# A4_INSAGE_02.net
KiCad netlist of a schematic drawn in Altium Designer
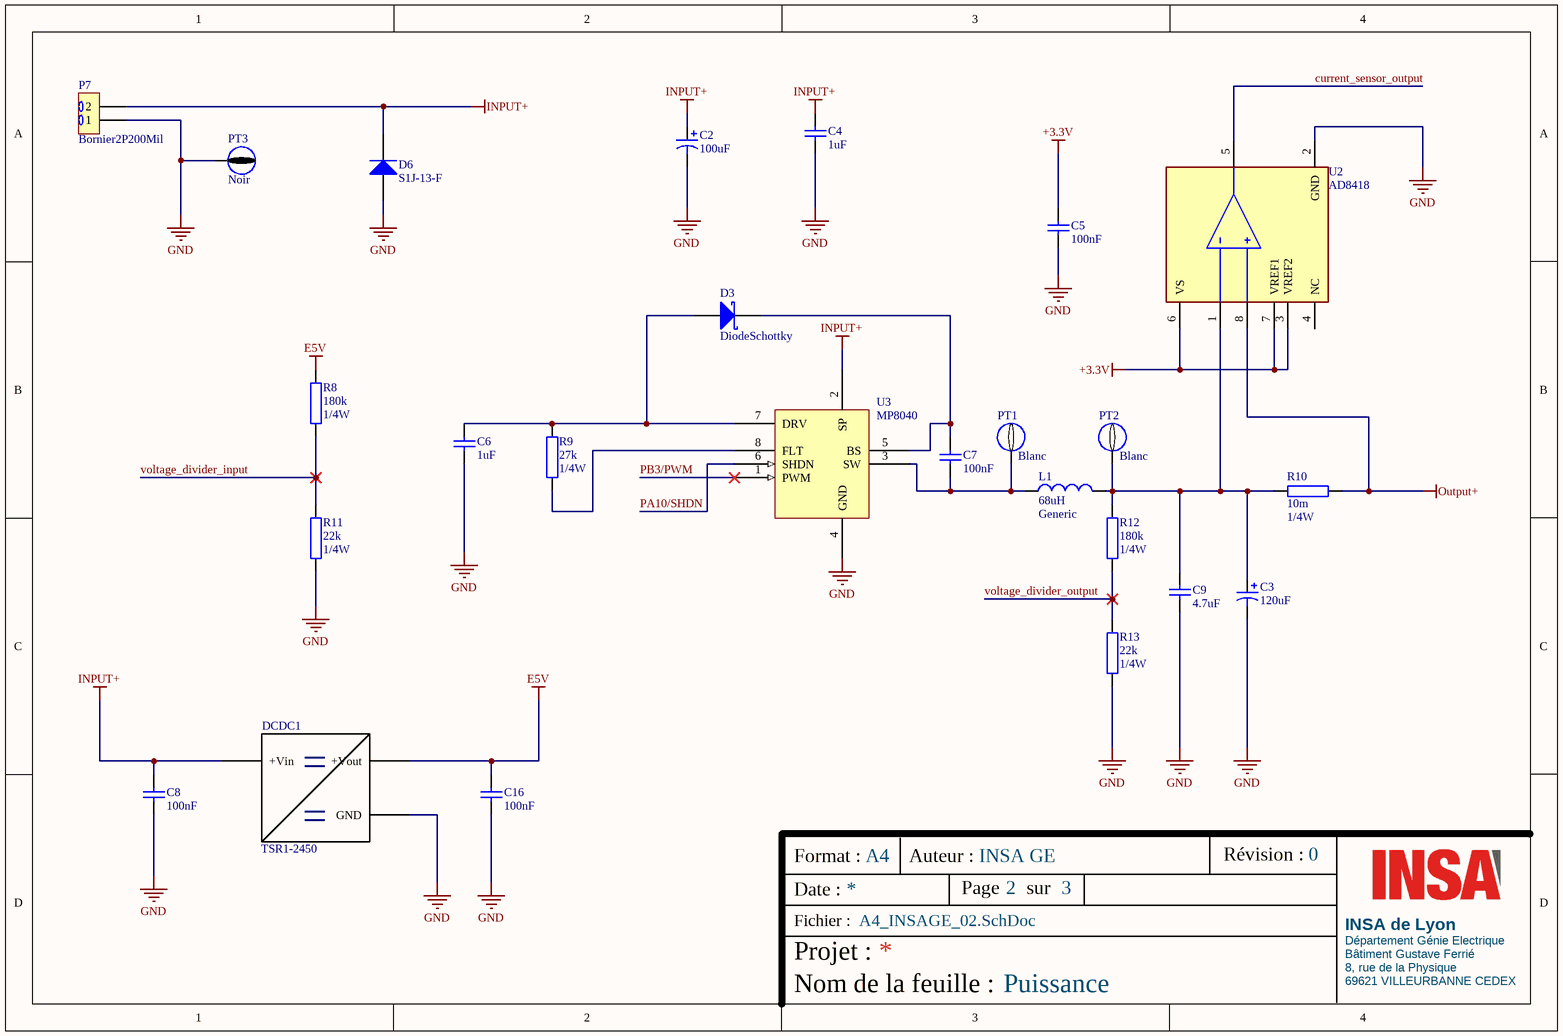
[diagram p0: A4_INSAGE_02.SchDoc]

(export (version "E")
  (design (tool "Eeschema 10.0.6"))
  (components
    (comp (ref "C2")
      (value "100uF")
      (footprint "CAPRAD10diax9.5")
      (fields (field (name "Comment") "Condensateur Pol") (field (name "PUBLISHER") "Altium Limited"))
      (libsource (lib "Altium_CREATE_2026") (part "Condensateur Pol"))
    )
    (comp (ref "C3")
      (value "120uF")
      (footprint "CAPRAD10diax9.5")
      (fields (field (name "Comment") "Condensateur Pol") (field (name "PUBLISHER") "Altium Limited"))
      (libsource (lib "Altium_CREATE_2026") (part "Condensateur Pol"))
    )
    (comp (ref "C4")
      (value "1uF")
      (footprint "1206_C")
      (fields (field (name "Comment") "Condensateur NON pol") (field (name "PUBLISHER") "Altium Limited"))
      (libsource (lib "Altium_CREATE_2026") (part "Condensateur NON pol"))
    )
    (comp (ref "C5")
      (value "100nF")
      (footprint "1206_C")
      (fields (field (name "Comment") "Condensateur NON pol") (field (name "PUBLISHER") "Altium Limited"))
      (libsource (lib "Altium_CREATE_2026") (part "Condensateur NON pol"))
    )
    (comp (ref "C6")
      (value "1uF")
      (footprint "1206_C")
      (fields (field (name "Comment") "Condensateur NON pol") (field (name "PUBLISHER") "Altium Limited"))
      (libsource (lib "Altium_CREATE_2026") (part "Condensateur NON pol"))
    )
    (comp (ref "C7")
      (value "100nF")
      (footprint "1206_C")
      (fields (field (name "Comment") "Condensateur NON pol") (field (name "PUBLISHER") "Altium Limited"))
      (libsource (lib "Altium_CREATE_2026") (part "Condensateur NON pol"))
    )
    (comp (ref "C8")
      (value "100nF")
      (footprint "1206_C")
      (fields (field (name "Comment") "Condensateur NON pol") (field (name "PUBLISHER") "Altium Limited"))
      (libsource (lib "Altium_CREATE_2026") (part "Condensateur NON pol"))
    )
    (comp (ref "C9")
      (value "4.7uF")
      (footprint "1206_C")
      (fields (field (name "Comment") "Condensateur NON pol") (field (name "PUBLISHER") "Altium Limited"))
      (libsource (lib "Altium_CREATE_2026") (part "Condensateur NON pol"))
    )
    (comp (ref "C16")
      (value "100nF")
      (footprint "1206_C")
      (fields (field (name "Comment") "Condensateur NON pol") (field (name "PUBLISHER") "Altium Limited"))
      (libsource (lib "Altium_CREATE_2026") (part "Condensateur NON pol"))
    )
    (comp (ref "D3")
      (value "DiodeSchottky")
      (footprint "DO-41")
      (description "Low drop power Schottky rectifier")
      (fields (field (name "PUBLISHER") "Altium Limited"))
      (libsource (lib "Altium_CREATE_2026") (part "1N5819"))
    )
    (comp (ref "D6")
      (value "S1J-13-F")
      (footprint "SMA (DO-214AC)")
      (description "Diode standard de redressement 600V 1A")
      (libsource (lib "Altium_CREATE_2026") (part "S1J-13-F"))
    )
    (comp (ref "DCDC1")
      (value "TSR1-2450")
      (footprint "TSR1Serie-1A")
      (description "DC/DC 6,5/36 -> 5V 1A")
      (libsource (lib "Altium_CREATE_2026") (part "TSR1-2450"))
    )
    (comp (ref "L1")
      (value "Generic")
      (footprint "7447709680")
      (description "Inductance 7447709680 Würth")
      (fields (field (name "ALTIUM_VALUE") "68uH") (field (name "PUBLISHER") "Altium Limited"))
      (libsource (lib "Altium_CREATE_2026") (part "Würth_7447709680"))
    )
    (comp (ref "P7")
      (value "Bornier2P200Mil")
      (footprint "BORN2PIN200MIL")
      (description "Bornier 2P 200mil")
      (fields (field (name "PUBLISHER") "Altium Limited"))
      (libsource (lib "Altium_CREATE_2026") (part "Bornier2P200Mil"))
    )
    (comp (ref "PT1")
      (value "Blanc")
      (footprint "PTest1.32mm")
      (description "Point de test PCB, Blanc, Montage traversant, 1.32 mm")
      (libsource (lib "Altium_CREATE_2026") (part "PTest_Blanc"))
    )
    (comp (ref "PT2")
      (value "Blanc")
      (footprint "PTest1.32mm")
      (description "Point de test PCB, Blanc, Montage traversant, 1.32 mm")
      (libsource (lib "Altium_CREATE_2026") (part "PTest_Blanc"))
    )
    (comp (ref "PT3")
      (value "Noir")
      (footprint "PTest1.32mm")
      (description "Point de test PCB, Noir, Montage traversant, 1.32 mm")
      (libsource (lib "Altium_CREATE_2026") (part "PTest_Noir"))
    )
    (comp (ref "R8")
      (value "180k")
      (footprint "1206_R")
      (description "Resistor")
      (fields
        (field (name "PUISSANCE") "1/4W")
        (field (name "Comment") "Resistance")
        (field (name "PUBLISHER") "Altium Limited")
      )
      (libsource (lib "Altium_CREATE_2026") (part "Resistance"))
    )
    (comp (ref "R9")
      (value "27k")
      (footprint "1206_R")
      (description "Resistor")
      (fields
        (field (name "PUISSANCE") "1/4W")
        (field (name "Comment") "Resistance")
        (field (name "PUBLISHER") "Altium Limited")
      )
      (libsource (lib "Altium_CREATE_2026") (part "Resistance"))
    )
    (comp (ref "R10")
      (value "10m")
      (footprint "1206_R")
      (description "Resistor")
      (fields
        (field (name "PUISSANCE") "1/4W")
        (field (name "Comment") "Resistance")
        (field (name "PUBLISHER") "Altium Limited")
      )
      (libsource (lib "Altium_CREATE_2026") (part "Resistance"))
    )
    (comp (ref "R11")
      (value "22k")
      (footprint "1206_R")
      (description "Resistor")
      (fields
        (field (name "PUISSANCE") "1/4W")
        (field (name "Comment") "Resistance")
        (field (name "PUBLISHER") "Altium Limited")
      )
      (libsource (lib "Altium_CREATE_2026") (part "Resistance"))
    )
    (comp (ref "R12")
      (value "180k")
      (footprint "1206_R")
      (description "Resistor")
      (fields
        (field (name "PUISSANCE") "1/4W")
        (field (name "Comment") "Resistance")
        (field (name "PUBLISHER") "Altium Limited")
      )
      (libsource (lib "Altium_CREATE_2026") (part "Resistance"))
    )
    (comp (ref "R13")
      (value "22k")
      (footprint "1206_R")
      (description "Resistor")
      (fields
        (field (name "PUISSANCE") "1/4W")
        (field (name "Comment") "Resistance")
        (field (name "PUBLISHER") "Altium Limited")
      )
      (libsource (lib "Altium_CREATE_2026") (part "Resistance"))
    )
    (comp (ref "U2")
      (value "AD8418")
      (footprint "SOIC-8-150")
      (description "IC Current Sensor")
      (libsource (lib "Altium_CREATE_2026") (part "AD8418"))
    )
    (comp (ref "U3")
      (value "MP8040")
      (footprint "SOIC-8-150")
      (description "9A, 24V Integrated Half-Bridge")
      (libsource (lib "Altium_CREATE_2026") (part "MP8040"))
    )
  )
  (nets
    (net (code "1") (name "+3.3V") (class "Default")
      (node (ref "C5") (pin "2") (pinfunction "2_2") (pintype "passive"))
      (node (ref "U2") (pin "3") (pinfunction "VREF2_3") (pintype "power_in"))
      (node (ref "U2") (pin "6") (pinfunction "VS_6") (pintype "power_in"))
      (node (ref "U2") (pin "7") (pinfunction "VREF1_7") (pintype "power_in"))
    )
    (net (code "2") (name "/PA10{slash}SHDN") (class "Default")
      (node (ref "U3") (pin "6") (pinfunction "SHDN_6") (pintype "input"))
    )
    (net (code "3") (name "/PB3{slash}PWM") (class "Default")
      (node (ref "U3") (pin "1") (pinfunction "PWM_1") (pintype "input+no_connect"))
    )
    (net (code "4") (name "/current_sensor_output") (class "Default")
      (node (ref "U2") (pin "5") (pinfunction "OUT_5") (pintype "passive"))
    )
    (net (code "5") (name "/voltage_divider_input") (class "Default")
      (node (ref "R11") (pin "2") (pinfunction "2_2") (pintype "passive"))
      (node (ref "R8") (pin "1") (pinfunction "1_1") (pintype "passive"))
    )
    (net (code "6") (name "/voltage_divider_output") (class "Default")
      (node (ref "R12") (pin "1") (pinfunction "1_1") (pintype "passive"))
      (node (ref "R13") (pin "2") (pinfunction "2_2") (pintype "passive"))
    )
    (net (code "7") (name "E5V") (class "Default")
      (node (ref "C16") (pin "2") (pinfunction "2_2") (pintype "passive"))
      (node (ref "DCDC1") (pin "3") (pinfunction "+Vout_3") (pintype "power_in"))
      (node (ref "R8") (pin "2") (pinfunction "2_2") (pintype "passive"))
    )
    (net (code "8") (name "GND") (class "Default")
      (node (ref "C16") (pin "1") (pinfunction "1_1") (pintype "passive"))
      (node (ref "C2") (pin "2") (pinfunction "2_2") (pintype "passive"))
      (node (ref "C3") (pin "2") (pinfunction "2_2") (pintype "passive"))
      (node (ref "C4") (pin "1") (pinfunction "1_1") (pintype "passive"))
      (node (ref "C5") (pin "1") (pinfunction "1_1") (pintype "passive"))
      (node (ref "C6") (pin "1") (pinfunction "1_1") (pintype "passive"))
      (node (ref "C8") (pin "1") (pinfunction "1_1") (pintype "passive"))
      (node (ref "C9") (pin "1") (pinfunction "1_1") (pintype "passive"))
      (node (ref "D6") (pin "1") (pinfunction "A_1") (pintype "passive"))
      (node (ref "DCDC1") (pin "2") (pinfunction "GND_2") (pintype "power_in"))
      (node (ref "P7") (pin "1") (pinfunction "1_1") (pintype "passive"))
      (node (ref "PT3") (pin "1") (pinfunction "1_1") (pintype "passive"))
      (node (ref "R11") (pin "1") (pinfunction "1_1") (pintype "passive"))
      (node (ref "R13") (pin "1") (pinfunction "1_1") (pintype "passive"))
      (node (ref "U2") (pin "2") (pinfunction "GND_2") (pintype "power_in"))
      (node (ref "U3") (pin "4") (pinfunction "GND_4") (pintype "power_in"))
    )
    (net (code "9") (name "INPUT+") (class "Default")
      (node (ref "C2") (pin "1") (pinfunction "1_1") (pintype "passive"))
      (node (ref "C4") (pin "2") (pinfunction "2_2") (pintype "passive"))
      (node (ref "C8") (pin "2") (pinfunction "2_2") (pintype "passive"))
      (node (ref "D6") (pin "2") (pinfunction "K_2") (pintype "passive"))
      (node (ref "DCDC1") (pin "1") (pinfunction "+Vin_1") (pintype "power_in"))
      (node (ref "P7") (pin "2") (pinfunction "2_2") (pintype "passive"))
      (node (ref "U3") (pin "2") (pinfunction "SP_2") (pintype "power_in"))
    )
    (net (code "10") (name "Net-(D3-A)") (class "Default")
      (node (ref "C6") (pin "2") (pinfunction "2_2") (pintype "passive"))
      (node (ref "D3") (pin "1") (pinfunction "A_1") (pintype "passive"))
      (node (ref "R9") (pin "2") (pinfunction "2_2") (pintype "passive"))
      (node (ref "U3") (pin "7") (pinfunction "DRV_7") (pintype "power_in"))
    )
    (net (code "11") (name "Net-(D3-K)") (class "Default")
      (node (ref "C7") (pin "2") (pinfunction "2_2") (pintype "passive"))
      (node (ref "D3") (pin "3") (pinfunction "K_3") (pintype "passive"))
      (node (ref "U3") (pin "5") (pinfunction "BS_5") (pintype "passive"))
    )
    (net (code "12") (name "Net-(U2--IN)") (class "Default")
      (node (ref "C3") (pin "1") (pinfunction "1_1") (pintype "passive"))
      (node (ref "C9") (pin "2") (pinfunction "2_2") (pintype "passive"))
      (node (ref "L1") (pin "2") (pinfunction "2_2") (pintype "passive"))
      (node (ref "PT2") (pin "1") (pinfunction "1_1") (pintype "passive"))
      (node (ref "R10") (pin "2") (pinfunction "2_2") (pintype "passive"))
      (node (ref "R12") (pin "2") (pinfunction "2_2") (pintype "passive"))
      (node (ref "U2") (pin "1") (pinfunction "-IN_1") (pintype "tri_state"))
    )
    (net (code "13") (name "Net-(U3-FLT)") (class "Default")
      (node (ref "R9") (pin "1") (pinfunction "1_1") (pintype "passive"))
      (node (ref "U3") (pin "8") (pinfunction "FLT_8") (pintype "open_collector"))
    )
    (net (code "14") (name "Net-(U3-SW)") (class "Default")
      (node (ref "C7") (pin "1") (pinfunction "1_1") (pintype "passive"))
      (node (ref "L1") (pin "1") (pinfunction "1_1") (pintype "passive"))
      (node (ref "PT1") (pin "1") (pinfunction "1_1") (pintype "passive"))
      (node (ref "U3") (pin "3") (pinfunction "SW_3") (pintype "power_in"))
    )
    (net (code "15") (name "Output+") (class "Default")
      (node (ref "R10") (pin "1") (pinfunction "1_1") (pintype "passive"))
      (node (ref "U2") (pin "8") (pinfunction "+IN_8") (pintype "tri_state"))
    )
    (net (code "16") (name "unconnected-(U2-NC-Pad4)") (class "Default")
      (node (ref "U2") (pin "4") (pinfunction "NC_4") (pintype "passive"))
    )
  )
)
